# mmcaudio-analog-in.net
KiCad netlist of a schematic drawn in EAGLE
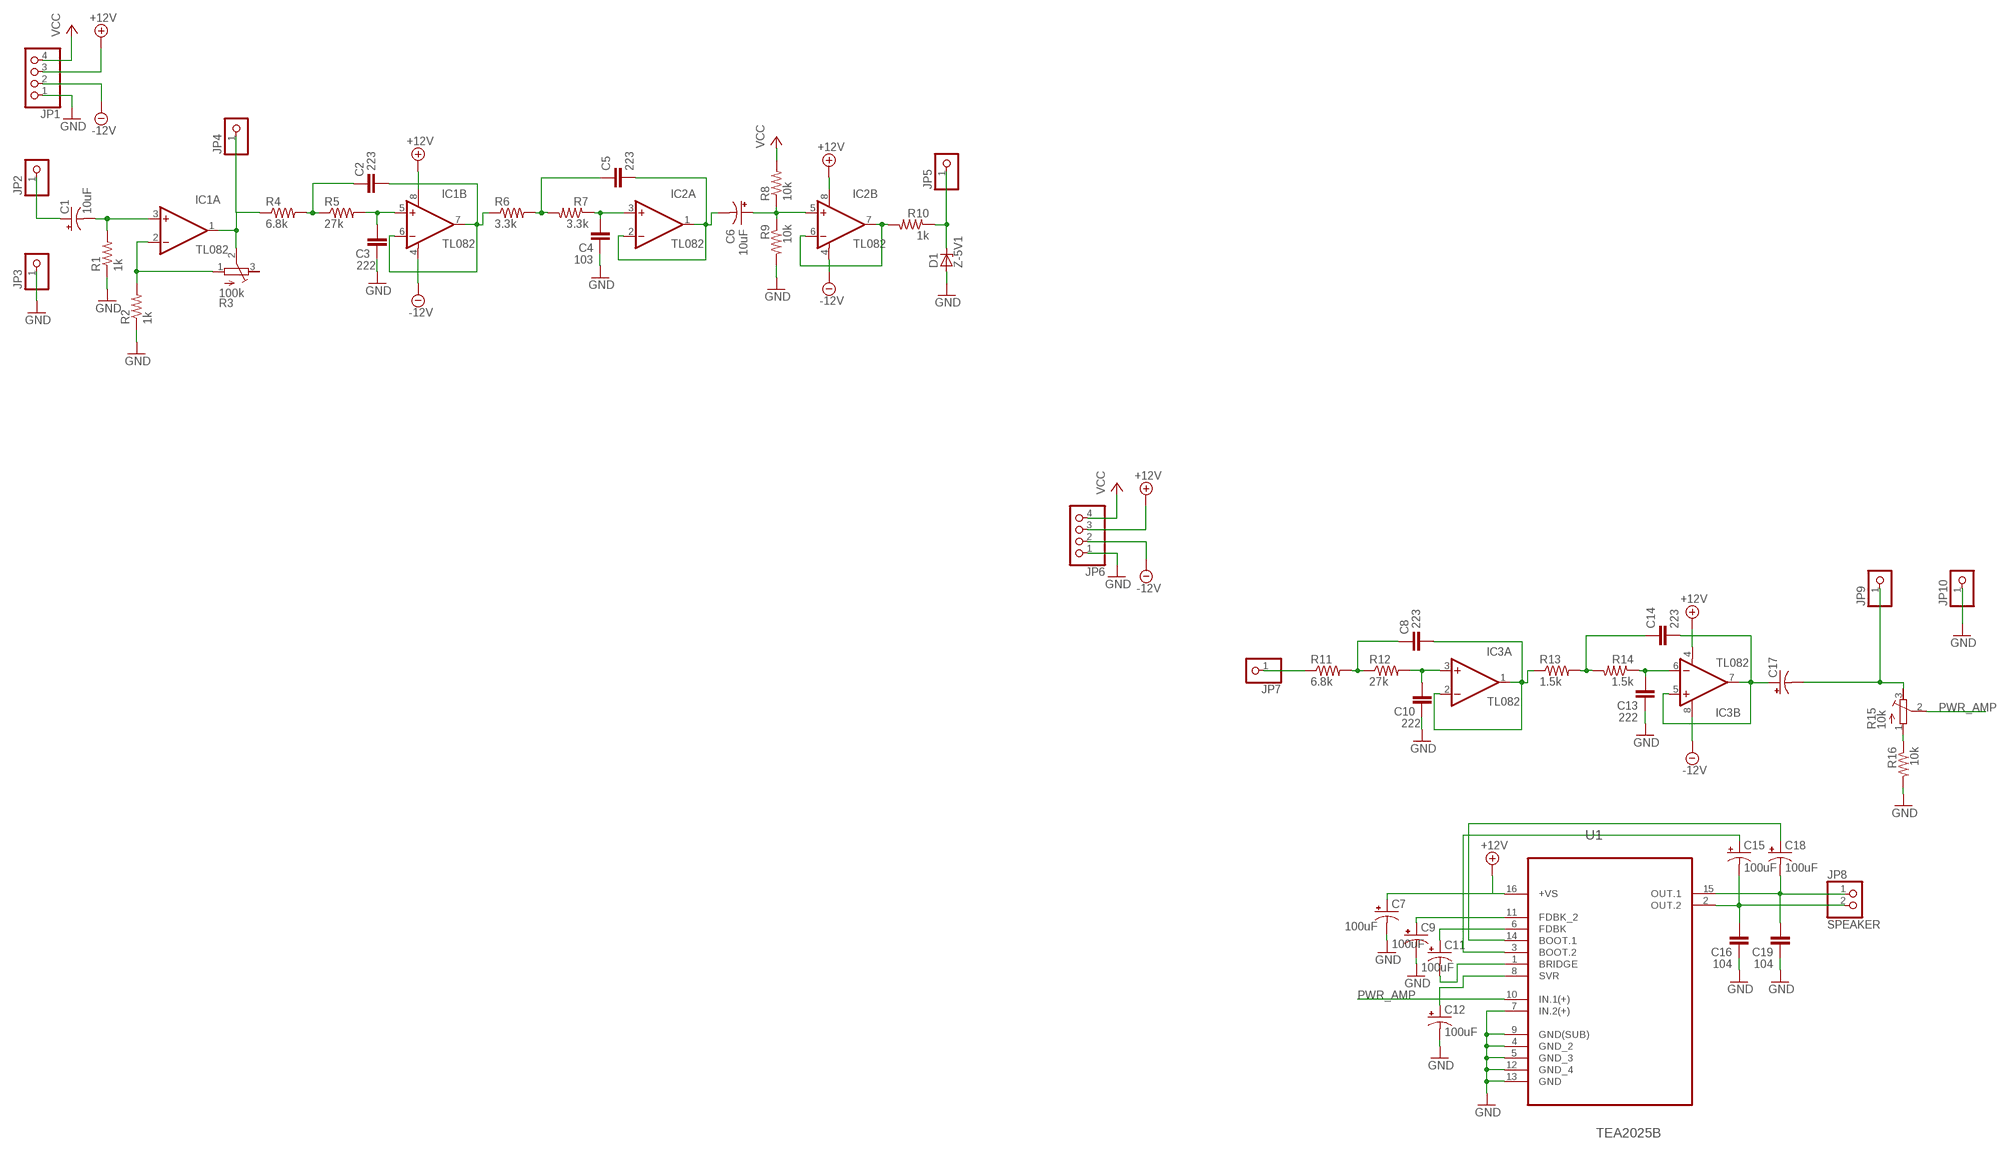
[diagram p0: schematic, sheet 1]

(export (version "E")
  (design (tool "Eeschema 10.0.6"))
  (components
    (comp (ref "C1")
      (value "10uF")
      (footprint "eagle-import:POL-CAP-COMMON")
      (libsource (lib "eagle-import") (part "CPOL-USSANYO_D"))
    )
    (comp (ref "C2")
      (value "223")
      (footprint "eagle-import:C025-060X050")
      (libsource (lib "eagle-import") (part "C-EUCERAMIC-CAP-COMMON"))
    )
    (comp (ref "C3")
      (value "222")
      (footprint "eagle-import:C025-060X050")
      (libsource (lib "eagle-import") (part "C-EUCERAMIC-CAP-COMMON"))
    )
    (comp (ref "C4")
      (value "103")
      (footprint "eagle-import:C025-060X050")
      (libsource (lib "eagle-import") (part "C-EUCERAMIC-CAP-COMMON"))
    )
    (comp (ref "C5")
      (value "223")
      (footprint "eagle-import:C025-060X050")
      (libsource (lib "eagle-import") (part "C-EUCERAMIC-CAP-COMMON"))
    )
    (comp (ref "C6")
      (value "10uF")
      (footprint "eagle-import:POL-CAP-COMMON")
      (libsource (lib "eagle-import") (part "CPOL-USSANYO_D"))
    )
    (comp (ref "C7")
      (value "100uF")
      (footprint "eagle-import:POL-CAP-COMMON")
      (libsource (lib "eagle-import") (part "CPOL-USSANYO_D"))
    )
    (comp (ref "C8")
      (value "223")
      (footprint "eagle-import:C025-060X050")
      (libsource (lib "eagle-import") (part "C-EUCERAMIC-CAP-COMMON"))
    )
    (comp (ref "C9")
      (value "100uF")
      (footprint "eagle-import:POL-CAP-COMMON")
      (libsource (lib "eagle-import") (part "CPOL-USSANYO_D"))
    )
    (comp (ref "C10")
      (value "222")
      (footprint "eagle-import:C025-060X050")
      (libsource (lib "eagle-import") (part "C-EUCERAMIC-CAP-COMMON"))
    )
    (comp (ref "C11")
      (value "100uF")
      (footprint "eagle-import:POL-CAP-COMMON")
      (libsource (lib "eagle-import") (part "CPOL-USSANYO_D"))
    )
    (comp (ref "C12")
      (value "100uF")
      (footprint "eagle-import:POL-CAP-COMMON")
      (libsource (lib "eagle-import") (part "CPOL-USSANYO_D"))
    )
    (comp (ref "C13")
      (value "222")
      (footprint "eagle-import:C025-060X050")
      (libsource (lib "eagle-import") (part "C-EUCERAMIC-CAP-COMMON"))
    )
    (comp (ref "C14")
      (value "223")
      (footprint "eagle-import:C025-060X050")
      (libsource (lib "eagle-import") (part "C-EUCERAMIC-CAP-COMMON"))
    )
    (comp (ref "C15")
      (value "100uF")
      (footprint "eagle-import:POL-CAP-COMMON")
      (libsource (lib "eagle-import") (part "CPOL-USSANYO_D"))
    )
    (comp (ref "C16")
      (value "104")
      (footprint "eagle-import:C025-060X050")
      (libsource (lib "eagle-import") (part "C-EUCERAMIC-CAP-COMMON"))
    )
    (comp (ref "C17")
      (value "CPOL-USSANYO_D")
      (footprint "eagle-import:POL-CAP-COMMON")
      (libsource (lib "eagle-import") (part "CPOL-USSANYO_D"))
    )
    (comp (ref "C18")
      (value "100uF")
      (footprint "eagle-import:POL-CAP-COMMON")
      (libsource (lib "eagle-import") (part "CPOL-USSANYO_D"))
    )
    (comp (ref "C19")
      (value "104")
      (footprint "eagle-import:C025-060X050")
      (libsource (lib "eagle-import") (part "C-EUCERAMIC-CAP-COMMON"))
    )
    (comp (ref "D1")
      (value "Z-5V1")
      (footprint "eagle-import:DO35Z7")
      (libsource (lib "eagle-import") (part "Z-5V1"))
    )
    (comp (ref "IC1")
      (value "TL082")
      (footprint "eagle-import:DIP08")
      (libsource (lib "eagle-import") (part "TL082"))
    )
    (comp (ref "IC2")
      (value "TL082")
      (footprint "eagle-import:DIP08")
      (libsource (lib "eagle-import") (part "TL082"))
    )
    (comp (ref "IC3")
      (value "TL082")
      (footprint "eagle-import:DIP08")
      (libsource (lib "eagle-import") (part "TL082"))
    )
    (comp (ref "JP1")
      (value "PINHD-1X4")
      (footprint "eagle-import:1X04")
      (libsource (lib "eagle-import") (part "PINHD-1X4"))
    )
    (comp (ref "JP2")
      (value "PINHD-1X1")
      (footprint "eagle-import:1X01")
      (libsource (lib "eagle-import") (part "PINHD-1X1"))
    )
    (comp (ref "JP3")
      (value "PINHD-1X1")
      (footprint "eagle-import:1X01")
      (libsource (lib "eagle-import") (part "PINHD-1X1"))
    )
    (comp (ref "JP4")
      (value "PINHD-1X1")
      (footprint "eagle-import:1X01")
      (libsource (lib "eagle-import") (part "PINHD-1X1"))
    )
    (comp (ref "JP5")
      (value "PINHD-1X1")
      (footprint "eagle-import:1X01")
      (libsource (lib "eagle-import") (part "PINHD-1X1"))
    )
    (comp (ref "JP6")
      (value "PINHD-1X4")
      (footprint "eagle-import:1X04")
      (libsource (lib "eagle-import") (part "PINHD-1X4"))
    )
    (comp (ref "JP7")
      (value "PINHD-1X1")
      (footprint "eagle-import:1X01")
      (libsource (lib "eagle-import") (part "PINHD-1X1"))
    )
    (comp (ref "JP8")
      (value "SPEAKER")
      (footprint "eagle-import:1X02_0.5_")
      (libsource (lib "eagle-import") (part "PINHD-1X20.5{dblquote}"))
    )
    (comp (ref "JP9")
      (value "PINHD-1X1")
      (footprint "eagle-import:1X01")
      (libsource (lib "eagle-import") (part "PINHD-1X1"))
    )
    (comp (ref "JP10")
      (value "PINHD-1X1")
      (footprint "eagle-import:1X01")
      (libsource (lib "eagle-import") (part "PINHD-1X1"))
    )
    (comp (ref "R1")
      (value "1k")
      (footprint "eagle-import:R-US-COMMON")
      (libsource (lib "eagle-import") (part "R-US_0207/10"))
    )
    (comp (ref "R2")
      (value "1k")
      (footprint "eagle-import:R-US-COMMON")
      (libsource (lib "eagle-import") (part "R-US_0207/10"))
    )
    (comp (ref "R3")
      (value "100k")
      (footprint "eagle-import:RTRIM-COMMON")
      (libsource (lib "eagle-import") (part "R-TRIMM64W"))
    )
    (comp (ref "R4")
      (value "6.8k")
      (footprint "eagle-import:R-US-COMMON")
      (libsource (lib "eagle-import") (part "R-US_0207/10"))
    )
    (comp (ref "R5")
      (value "27k")
      (footprint "eagle-import:R-US-COMMON")
      (libsource (lib "eagle-import") (part "R-US_0207/10"))
    )
    (comp (ref "R6")
      (value "3.3k")
      (footprint "eagle-import:R-US-COMMON")
      (libsource (lib "eagle-import") (part "R-US_0207/10"))
    )
    (comp (ref "R7")
      (value "3.3k")
      (footprint "eagle-import:R-US-COMMON")
      (libsource (lib "eagle-import") (part "R-US_0207/10"))
    )
    (comp (ref "R8")
      (value "10k")
      (footprint "eagle-import:R-US-COMMON")
      (libsource (lib "eagle-import") (part "R-US_0207/10"))
    )
    (comp (ref "R9")
      (value "10k")
      (footprint "eagle-import:R-US-COMMON")
      (libsource (lib "eagle-import") (part "R-US_0207/10"))
    )
    (comp (ref "R10")
      (value "1k")
      (footprint "eagle-import:R-US-COMMON")
      (libsource (lib "eagle-import") (part "R-US_0207/10"))
    )
    (comp (ref "R11")
      (value "6.8k")
      (footprint "eagle-import:R-US-COMMON")
      (libsource (lib "eagle-import") (part "R-US_0207/10"))
    )
    (comp (ref "R12")
      (value "27k")
      (footprint "eagle-import:R-US-COMMON")
      (libsource (lib "eagle-import") (part "R-US_0207/10"))
    )
    (comp (ref "R13")
      (value "1.5k")
      (footprint "eagle-import:R-US-COMMON")
      (libsource (lib "eagle-import") (part "R-US_0207/10"))
    )
    (comp (ref "R14")
      (value "1.5k")
      (footprint "eagle-import:R-US-COMMON")
      (libsource (lib "eagle-import") (part "R-US_0207/10"))
    )
    (comp (ref "R15")
      (value "10k")
      (footprint "eagle-import:RTRIM-COMMON")
      (libsource (lib "eagle-import") (part "R-TRIMM64W"))
    )
    (comp (ref "R16")
      (value "10k")
      (footprint "eagle-import:R-US-COMMON")
      (libsource (lib "eagle-import") (part "R-US_0207/10"))
    )
    (comp (ref "U1")
      (value "TEA2025B")
      (footprint "eagle-import:DIP254P762X510-16")
      (libsource (lib "eagle-import") (part "TEA2025B"))
    )
  )
  (nets
    (net (code "1") (name "+12V") (class "Default")
      (node (ref "C7") (pin "+") (pinfunction "+_+") (pintype "passive"))
      (node (ref "IC1") (pin "8") (pinfunction "V+_8") (pintype "power_in"))
      (node (ref "IC2") (pin "8") (pinfunction "V+_8") (pintype "power_in"))
      (node (ref "IC3") (pin "4") (pinfunction "V-_4") (pintype "power_in"))
      (node (ref "JP1") (pin "3") (pinfunction "3_3") (pintype "passive"))
      (node (ref "JP6") (pin "3") (pinfunction "3_3") (pintype "passive"))
      (node (ref "U1") (pin "16") (pinfunction "+VS_16") (pintype "power_in"))
    )
    (net (code "2") (name "-12V") (class "Default")
      (node (ref "IC1") (pin "4") (pinfunction "V-_4") (pintype "power_in"))
      (node (ref "IC2") (pin "4") (pinfunction "V-_4") (pintype "power_in"))
      (node (ref "IC3") (pin "8") (pinfunction "V+_8") (pintype "power_in"))
      (node (ref "JP1") (pin "2") (pinfunction "2_2") (pintype "passive"))
      (node (ref "JP6") (pin "2") (pinfunction "2_2") (pintype "passive"))
    )
    (net (code "3") (name "/PWR_AMP") (class "Default")
      (node (ref "R15") (pin "2") (pinfunction "S_2") (pintype "passive"))
      (node (ref "U1") (pin "10") (pinfunction "IN.1(+)_10") (pintype "input"))
    )
    (net (code "4") (name "GND") (class "Default")
      (node (ref "C10") (pin "1") (pinfunction "1_1") (pintype "passive"))
      (node (ref "C12") (pin "-") (pinfunction "-_-") (pintype "passive"))
      (node (ref "C13") (pin "1") (pinfunction "1_1") (pintype "passive"))
      (node (ref "C16") (pin "1") (pinfunction "1_1") (pintype "passive"))
      (node (ref "C19") (pin "1") (pinfunction "1_1") (pintype "passive"))
      (node (ref "C3") (pin "1") (pinfunction "1_1") (pintype "passive"))
      (node (ref "C4") (pin "1") (pinfunction "1_1") (pintype "passive"))
      (node (ref "C7") (pin "-") (pinfunction "-_-") (pintype "passive"))
      (node (ref "C9") (pin "-") (pinfunction "-_-") (pintype "passive"))
      (node (ref "D1") (pin "A") (pinfunction "A_A") (pintype "passive"))
      (node (ref "JP1") (pin "1") (pinfunction "1_1") (pintype "passive"))
      (node (ref "JP10") (pin "1") (pinfunction "1_1") (pintype "passive"))
      (node (ref "JP3") (pin "1") (pinfunction "1_1") (pintype "passive"))
      (node (ref "JP6") (pin "1") (pinfunction "1_1") (pintype "passive"))
      (node (ref "R1") (pin "1") (pinfunction "1_1") (pintype "passive"))
      (node (ref "R16") (pin "2") (pinfunction "2_2") (pintype "passive"))
      (node (ref "R2") (pin "1") (pinfunction "1_1") (pintype "passive"))
      (node (ref "R9") (pin "2") (pinfunction "2_2") (pintype "passive"))
      (node (ref "U1") (pin "12") (pinfunction "GND_4_12") (pintype "passive"))
      (node (ref "U1") (pin "13") (pinfunction "GND_13") (pintype "passive"))
      (node (ref "U1") (pin "4") (pinfunction "GND_2_4") (pintype "passive"))
      (node (ref "U1") (pin "5") (pinfunction "GND_3_5") (pintype "passive"))
      (node (ref "U1") (pin "7") (pinfunction "IN.2(+)_7") (pintype "input"))
      (node (ref "U1") (pin "9") (pinfunction "GND(SUB)_9") (pintype "passive"))
    )
    (net (code "5") (name "Net-(C1-Pad+)") (class "Default")
      (node (ref "C1") (pin "+") (pinfunction "+_+") (pintype "passive"))
      (node (ref "JP2") (pin "1") (pinfunction "1_1") (pintype "passive"))
    )
    (net (code "6") (name "Net-(C2-Pad1)") (class "Default")
      (node (ref "C2") (pin "1") (pinfunction "1_1") (pintype "passive"))
      (node (ref "R4") (pin "2") (pinfunction "2_2") (pintype "passive"))
      (node (ref "R5") (pin "1") (pinfunction "1_1") (pintype "passive"))
    )
    (net (code "7") (name "Net-(C5-Pad1)") (class "Default")
      (node (ref "C5") (pin "1") (pinfunction "1_1") (pintype "passive"))
      (node (ref "R6") (pin "2") (pinfunction "2_2") (pintype "passive"))
      (node (ref "R7") (pin "2") (pinfunction "2_2") (pintype "passive"))
    )
    (net (code "8") (name "Net-(C8-Pad1)") (class "Default")
      (node (ref "C8") (pin "1") (pinfunction "1_1") (pintype "passive"))
      (node (ref "R11") (pin "2") (pinfunction "2_2") (pintype "passive"))
      (node (ref "R12") (pin "1") (pinfunction "1_1") (pintype "passive"))
    )
    (net (code "9") (name "Net-(C14-Pad1)") (class "Default")
      (node (ref "C14") (pin "1") (pinfunction "1_1") (pintype "passive"))
      (node (ref "R13") (pin "2") (pinfunction "2_2") (pintype "passive"))
      (node (ref "R14") (pin "2") (pinfunction "2_2") (pintype "passive"))
    )
    (net (code "10") (name "Net-(D1-PadC)") (class "Default")
      (node (ref "D1") (pin "C") (pinfunction "C_C") (pintype "passive"))
      (node (ref "JP5") (pin "1") (pinfunction "1_1") (pintype "passive"))
      (node (ref "R10") (pin "1") (pinfunction "1_1") (pintype "passive"))
    )
    (net (code "11") (name "Net-(IC1A-+IN)") (class "Default")
      (node (ref "C1") (pin "-") (pinfunction "-_-") (pintype "passive"))
      (node (ref "IC1") (pin "3") (pinfunction "+IN_3") (pintype "input"))
      (node (ref "R1") (pin "2") (pinfunction "2_2") (pintype "passive"))
    )
    (net (code "12") (name "Net-(IC1A--IN)") (class "Default")
      (node (ref "IC1") (pin "2") (pinfunction "-IN_2") (pintype "input"))
      (node (ref "R2") (pin "2") (pinfunction "2_2") (pintype "passive"))
      (node (ref "R3") (pin "1") (pinfunction "A_1") (pintype "passive"))
    )
    (net (code "13") (name "Net-(IC1A-OUT)") (class "Default")
      (node (ref "IC1") (pin "1") (pinfunction "OUT_1") (pintype "output"))
      (node (ref "JP4") (pin "1") (pinfunction "1_1") (pintype "passive"))
      (node (ref "R3") (pin "2") (pinfunction "S_2") (pintype "passive"))
      (node (ref "R4") (pin "1") (pinfunction "1_1") (pintype "passive"))
    )
    (net (code "14") (name "Net-(IC1B-+IN)") (class "Default")
      (node (ref "C3") (pin "2") (pinfunction "2_2") (pintype "passive"))
      (node (ref "IC1") (pin "5") (pinfunction "+IN_5") (pintype "input"))
      (node (ref "R5") (pin "2") (pinfunction "2_2") (pintype "passive"))
    )
    (net (code "15") (name "Net-(IC1B--IN)") (class "Default")
      (node (ref "C2") (pin "2") (pinfunction "2_2") (pintype "passive"))
      (node (ref "IC1") (pin "6") (pinfunction "-IN_6") (pintype "input"))
      (node (ref "IC1") (pin "7") (pinfunction "OUT_7") (pintype "output"))
      (node (ref "R6") (pin "1") (pinfunction "1_1") (pintype "passive"))
    )
    (net (code "16") (name "Net-(IC2A-+IN)") (class "Default")
      (node (ref "C4") (pin "2") (pinfunction "2_2") (pintype "passive"))
      (node (ref "IC2") (pin "3") (pinfunction "+IN_3") (pintype "input"))
      (node (ref "R7") (pin "1") (pinfunction "1_1") (pintype "passive"))
    )
    (net (code "17") (name "Net-(IC2A--IN)") (class "Default")
      (node (ref "C5") (pin "2") (pinfunction "2_2") (pintype "passive"))
      (node (ref "C6") (pin "-") (pinfunction "-_-") (pintype "passive"))
      (node (ref "IC2") (pin "1") (pinfunction "OUT_1") (pintype "output"))
      (node (ref "IC2") (pin "2") (pinfunction "-IN_2") (pintype "input"))
    )
    (net (code "18") (name "Net-(IC2B-+IN)") (class "Default")
      (node (ref "C6") (pin "+") (pinfunction "+_+") (pintype "passive"))
      (node (ref "IC2") (pin "5") (pinfunction "+IN_5") (pintype "input"))
      (node (ref "R8") (pin "1") (pinfunction "1_1") (pintype "passive"))
      (node (ref "R9") (pin "1") (pinfunction "1_1") (pintype "passive"))
    )
    (net (code "19") (name "Net-(IC2B--IN)") (class "Default")
      (node (ref "IC2") (pin "6") (pinfunction "-IN_6") (pintype "input"))
      (node (ref "IC2") (pin "7") (pinfunction "OUT_7") (pintype "output"))
      (node (ref "R10") (pin "2") (pinfunction "2_2") (pintype "passive"))
    )
    (net (code "20") (name "Net-(IC3A-+IN)") (class "Default")
      (node (ref "C10") (pin "2") (pinfunction "2_2") (pintype "passive"))
      (node (ref "IC3") (pin "3") (pinfunction "+IN_3") (pintype "input"))
      (node (ref "R12") (pin "2") (pinfunction "2_2") (pintype "passive"))
    )
    (net (code "21") (name "Net-(IC3A--IN)") (class "Default")
      (node (ref "C8") (pin "2") (pinfunction "2_2") (pintype "passive"))
      (node (ref "IC3") (pin "1") (pinfunction "OUT_1") (pintype "output"))
      (node (ref "IC3") (pin "2") (pinfunction "-IN_2") (pintype "input"))
      (node (ref "R13") (pin "1") (pinfunction "1_1") (pintype "passive"))
    )
    (net (code "22") (name "Net-(IC3B-+IN)") (class "Default")
      (node (ref "C14") (pin "2") (pinfunction "2_2") (pintype "passive"))
      (node (ref "C17") (pin "+") (pinfunction "+_+") (pintype "passive"))
      (node (ref "IC3") (pin "5") (pinfunction "+IN_5") (pintype "input"))
      (node (ref "IC3") (pin "7") (pinfunction "OUT_7") (pintype "output"))
    )
    (net (code "23") (name "Net-(IC3B--IN)") (class "Default")
      (node (ref "C13") (pin "2") (pinfunction "2_2") (pintype "passive"))
      (node (ref "IC3") (pin "6") (pinfunction "-IN_6") (pintype "input"))
      (node (ref "R14") (pin "1") (pinfunction "1_1") (pintype "passive"))
    )
    (net (code "24") (name "Net-(JP7-Pad1)") (class "Default")
      (node (ref "JP7") (pin "1") (pinfunction "1_1") (pintype "passive"))
      (node (ref "R11") (pin "1") (pinfunction "1_1") (pintype "passive"))
    )
    (net (code "25") (name "Net-(R15-A)") (class "Default")
      (node (ref "R15") (pin "1") (pinfunction "A_1") (pintype "passive"))
      (node (ref "R16") (pin "1") (pinfunction "1_1") (pintype "passive"))
    )
    (net (code "26") (name "Net-(R15-E)") (class "Default")
      (node (ref "C17") (pin "-") (pinfunction "-_-") (pintype "passive"))
      (node (ref "JP9") (pin "1") (pinfunction "1_1") (pintype "passive"))
      (node (ref "R15") (pin "3") (pinfunction "E_3") (pintype "passive"))
    )
    (net (code "27") (name "Net-(U1-BOOT.1)") (class "Default")
      (node (ref "C18") (pin "+") (pinfunction "+_+") (pintype "passive"))
      (node (ref "U1") (pin "14") (pinfunction "BOOT.1_14") (pintype "passive"))
    )
    (net (code "28") (name "Net-(U1-BOOT.2)") (class "Default")
      (node (ref "C15") (pin "+") (pinfunction "+_+") (pintype "passive"))
      (node (ref "U1") (pin "3") (pinfunction "BOOT.2_3") (pintype "passive"))
    )
    (net (code "29") (name "Net-(U1-BRIDGE)") (class "Default")
      (node (ref "C11") (pin "-") (pinfunction "-_-") (pintype "passive"))
      (node (ref "U1") (pin "1") (pinfunction "BRIDGE_1") (pintype "passive"))
    )
    (net (code "30") (name "Net-(U1-FDBK)") (class "Default")
      (node (ref "C11") (pin "+") (pinfunction "+_+") (pintype "passive"))
      (node (ref "U1") (pin "6") (pinfunction "FDBK_6") (pintype "input"))
    )
    (net (code "31") (name "Net-(U1-FDBK_2)") (class "Default")
      (node (ref "C9") (pin "+") (pinfunction "+_+") (pintype "passive"))
      (node (ref "U1") (pin "11") (pinfunction "FDBK_2_11") (pintype "input"))
    )
    (net (code "32") (name "Net-(U1-OUT.1)") (class "Default")
      (node (ref "C18") (pin "-") (pinfunction "-_-") (pintype "passive"))
      (node (ref "C19") (pin "2") (pinfunction "2_2") (pintype "passive"))
      (node (ref "JP8") (pin "1") (pinfunction "1_1") (pintype "passive"))
      (node (ref "U1") (pin "15") (pinfunction "OUT.1_15") (pintype "output"))
    )
    (net (code "33") (name "Net-(U1-OUT.2)") (class "Default")
      (node (ref "C15") (pin "-") (pinfunction "-_-") (pintype "passive"))
      (node (ref "C16") (pin "2") (pinfunction "2_2") (pintype "passive"))
      (node (ref "JP8") (pin "2") (pinfunction "2_2") (pintype "passive"))
      (node (ref "U1") (pin "2") (pinfunction "OUT.2_2") (pintype "output"))
    )
    (net (code "34") (name "Net-(U1-SVR)") (class "Default")
      (node (ref "C12") (pin "+") (pinfunction "+_+") (pintype "passive"))
      (node (ref "U1") (pin "8") (pinfunction "SVR_8") (pintype "passive"))
    )
    (net (code "35") (name "VCC") (class "Default")
      (node (ref "JP1") (pin "4") (pinfunction "4_4") (pintype "passive"))
      (node (ref "JP6") (pin "4") (pinfunction "4_4") (pintype "passive"))
      (node (ref "R8") (pin "2") (pinfunction "2_2") (pintype "passive"))
    )
    (net (code "36") (name "unconnected-(R3-E-Pad3)") (class "Default")
      (node (ref "R3") (pin "3") (pinfunction "E_3") (pintype "passive"))
    )
  )
)
